# Sensors_and_MCU.net
KiCad netlist of a schematic drawn in Altium Designer
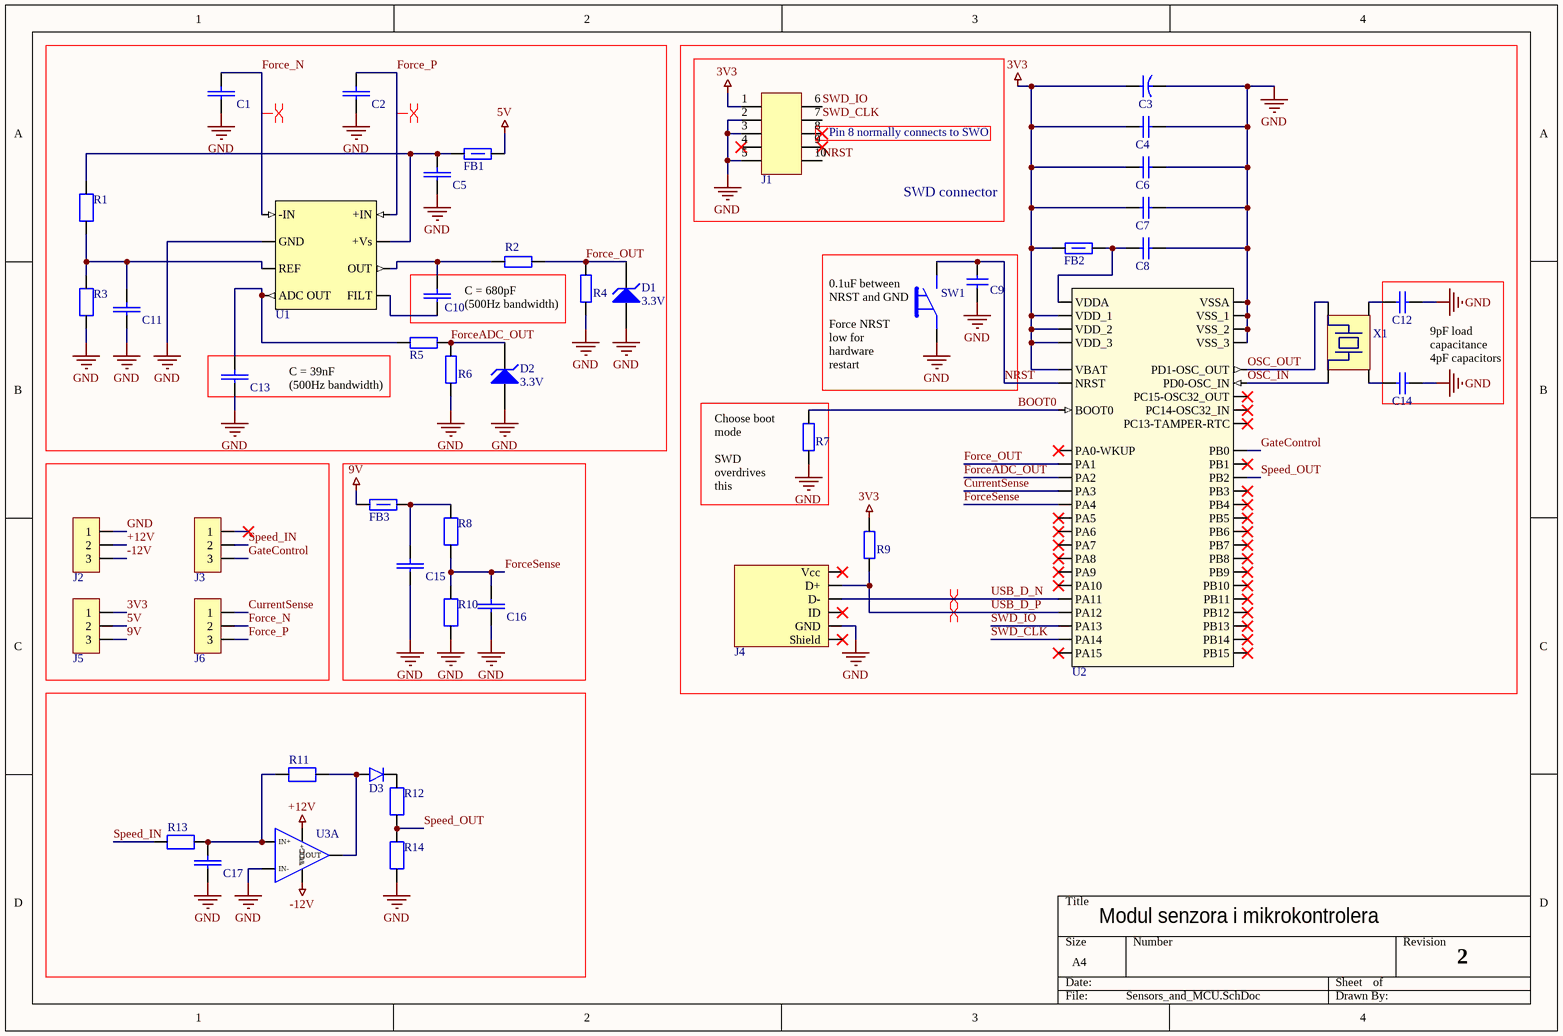
[diagram p0: Sensors_and_MCU.SchDoc]

(export (version "E")
  (design (tool "Eeschema 10.0.6"))
  (components
    (comp (ref "C1")
      (value "Capacitor-NP")
      (footprint "Footprints:C-NP")
      (libsource (lib "Symbols") (part "Capacitor-NP"))
    )
    (comp (ref "C2")
      (value "Capacitor-NP")
      (footprint "Footprints:C-NP")
      (libsource (lib "Symbols") (part "Capacitor-NP"))
    )
    (comp (ref "C3")
      (value "10uF")
      (footprint "CAPAE430X610D540L170X65N")
      (fields
        (field (name "PART NUMBER") "C_10uF_50V")
        (field (name "MANUFACTURER PART NUMBER") "EEE-FK1H100SR")
      )
      (libsource (lib "Database_Libs") (part "Capacitor_P"))
    )
    (comp (ref "C4")
      (value "100nF")
      (footprint "CAPC160X80X87L35N")
      (fields
        (field (name "PART NUMBER") "C_0603_100nF_50V")
        (field (name "MANUFACTURER PART NUMBER") "CC0603MRY5V9BB104")
      )
      (libsource (lib "Database_Libs") (part "Capacitor_NP"))
    )
    (comp (ref "C5")
      (value "Capacitor-NP")
      (footprint "Footprints:C-NP")
      (libsource (lib "Symbols") (part "Capacitor-NP"))
    )
    (comp (ref "C6")
      (value "100nF")
      (footprint "CAPC160X80X87L35N")
      (fields
        (field (name "PART NUMBER") "C_0603_100nF_50V")
        (field (name "MANUFACTURER PART NUMBER") "CC0603MRY5V9BB104")
      )
      (libsource (lib "Database_Libs") (part "Capacitor_NP"))
    )
    (comp (ref "C7")
      (value "100nF")
      (footprint "CAPC160X80X87L35N")
      (fields
        (field (name "PART NUMBER") "C_0603_100nF_50V")
        (field (name "MANUFACTURER PART NUMBER") "CC0603MRY5V9BB104")
      )
      (libsource (lib "Database_Libs") (part "Capacitor_NP"))
    )
    (comp (ref "C8")
      (value "100nF")
      (footprint "CAPC160X80X87L35N")
      (fields
        (field (name "PART NUMBER") "C_0603_100nF_50V")
        (field (name "MANUFACTURER PART NUMBER") "CC0603MRY5V9BB104")
      )
      (libsource (lib "Database_Libs") (part "Capacitor_NP"))
    )
    (comp (ref "C9")
      (value "100nF")
      (footprint "CAPC160X80X87L35N")
      (fields
        (field (name "PART NUMBER") "C_0603_100nF_50V")
        (field (name "MANUFACTURER PART NUMBER") "CC0603MRY5V9BB104")
      )
      (libsource (lib "Database_Libs") (part "Capacitor_NP"))
    )
    (comp (ref "C10")
      (value "Capacitor-NP")
      (footprint "Footprints:C-NP")
      (libsource (lib "Symbols") (part "Capacitor-NP"))
    )
    (comp (ref "C11")
      (value "Capacitor-NP")
      (footprint "Footprints:C-NP")
      (libsource (lib "Symbols") (part "Capacitor-NP"))
    )
    (comp (ref "C12")
      (value "4pF")
      (footprint "CAPC100X50X55L22N")
      (fields
        (field (name "PART NUMBER") "C_0402_4pF_25V")
        (field (name "MANUFACTURER PART NUMBER") "GRM0225C1E4R0CA03L")
      )
      (libsource (lib "Database_Libs") (part "Capacitor_NP"))
    )
    (comp (ref "C13")
      (value "Capacitor-NP")
      (footprint "Footprints:C-NP")
      (libsource (lib "Symbols") (part "Capacitor-NP"))
    )
    (comp (ref "C14")
      (value "4pF")
      (footprint "CAPC100X50X55L22N")
      (fields
        (field (name "PART NUMBER") "C_0402_4pF_25V")
        (field (name "MANUFACTURER PART NUMBER") "GRM0225C1E4R0CA03L")
      )
      (libsource (lib "Database_Libs") (part "Capacitor_NP"))
    )
    (comp (ref "C15")
      (value "Capacitor-NP")
      (footprint "Footprints:C-NP")
      (libsource (lib "Symbols") (part "Capacitor-NP"))
    )
    (comp (ref "C16")
      (value "Capacitor-NP")
      (footprint "Footprints:C-NP")
      (libsource (lib "Symbols") (part "Capacitor-NP"))
    )
    (comp (ref "C17")
      (value "Capacitor-NP")
      (footprint "Footprints:C-NP")
      (libsource (lib "Symbols") (part "Capacitor-NP"))
    )
    (comp (ref "D1")
      (value "Zener Diode")
      (fields (field (name "BV") "3.3V"))
      (libsource (lib "Simulation Generic Components") (part "Zener Diode"))
    )
    (comp (ref "D2")
      (value "Zener Diode")
      (fields (field (name "BV") "3.3V"))
      (libsource (lib "Simulation Generic Components") (part "Zener Diode"))
    )
    (comp (ref "D3")
      (value "Diode")
      (footprint "Footprints:Diode")
      (libsource (lib "Symbols") (part "Diode"))
    )
    (comp (ref "FB1")
      (value "BLM18HE152SH1D")
      (footprint "BEADC160X80X95L30N")
      (libsource (lib "Database_Libs") (part "Ferrite Bead"))
    )
    (comp (ref "FB2")
      (value "BLM18HE152SH1D")
      (footprint "BEADC160X80X95L30N")
      (libsource (lib "Database_Libs") (part "Ferrite Bead"))
    )
    (comp (ref "FB3")
      (value "BLM18HE152SH1D")
      (footprint "BEADC160X80X95L30N")
      (libsource (lib "Database_Libs") (part "Ferrite Bead"))
    )
    (comp (ref "J1")
      (value "Header_10P")
      (footprint "M50-3610542")
      (fields
        (field (name "PART NUMBER") "Header_2x5")
        (field (name "MANUFACTURER PART NUMBER") "M50-3610542")
      )
      (libsource (lib "Database_Libs") (part "Header_2x5"))
    )
    (comp (ref "J2")
      (value "Molex Micro-Latch")
      (footprint "Footprints:ScrewTerminal")
      (fields
        (field (name "PART NUMBER") "Molex Micro-Latch 1x3")
        (field (name "MANUFACTURER PART NUMBER") "53254-0370")
      )
      (libsource (lib "Database_Libs") (part "Header_1x3"))
    )
    (comp (ref "J3")
      (value "Molex Micro-Latch")
      (footprint "Footprints:ScrewTerminal")
      (fields
        (field (name "PART NUMBER") "Molex Micro-Latch 1x3")
        (field (name "MANUFACTURER PART NUMBER") "53254-0370")
      )
      (libsource (lib "Database_Libs") (part "Header_1x3"))
    )
    (comp (ref "J4")
      (value "USB")
      (footprint "USB_mini")
      (fields
        (field (name "PART NUMBER") "USB mini")
        (field (name "MANUFACTURER PART NUMBER") "UJ2-MBH-1-SMT-TR")
      )
      (libsource (lib "Database_Libs") (part "USB_5 pin"))
    )
    (comp (ref "J5")
      (value "Molex Micro-Latch")
      (footprint "Footprints:ScrewTerminal")
      (fields
        (field (name "PART NUMBER") "Molex Micro-Latch 1x3")
        (field (name "MANUFACTURER PART NUMBER") "53254-0370")
      )
      (libsource (lib "Database_Libs") (part "Header_1x3"))
    )
    (comp (ref "J6")
      (value "Molex Micro-Latch")
      (footprint "Footprints:ScrewTerminal")
      (fields
        (field (name "PART NUMBER") "Molex Micro-Latch 1x3")
        (field (name "MANUFACTURER PART NUMBER") "53254-0370")
      )
      (libsource (lib "Database_Libs") (part "Header_1x3"))
    )
    (comp (ref "R1")
      (value "100k")
      (footprint "Footprints:R-2W")
      (libsource (lib "Symbols") (part "Resistor"))
    )
    (comp (ref "R2")
      (value "1.5k")
      (footprint "RESC160X80X50L30N")
      (fields
        (field (name "PART NUMBER") "R_0603_1k5_0W1")
        (field (name "MANUFACTURER PART NUMBER") "RT0603FRE101K5L")
      )
      (libsource (lib "Database_Libs") (part "Resistor"))
    )
    (comp (ref "R3")
      (value "47k")
      (footprint "Footprints:R-2W")
      (libsource (lib "Symbols") (part "Resistor"))
    )
    (comp (ref "R4")
      (value "1.5k")
      (footprint "RESC160X80X50L30N")
      (fields
        (field (name "PART NUMBER") "R_0603_1k5_0W1")
        (field (name "MANUFACTURER PART NUMBER") "RT0603FRE101K5L")
      )
      (libsource (lib "Database_Libs") (part "Resistor"))
    )
    (comp (ref "R5")
      (value "1.5k")
      (footprint "RESC160X80X50L30N")
      (fields
        (field (name "PART NUMBER") "R_0603_1k5_0W1")
        (field (name "MANUFACTURER PART NUMBER") "RT0603FRE101K5L")
      )
      (libsource (lib "Database_Libs") (part "Resistor"))
    )
    (comp (ref "R6")
      (value "1.5k")
      (footprint "RESC160X80X50L30N")
      (fields
        (field (name "PART NUMBER") "R_0603_1k5_0W1")
        (field (name "MANUFACTURER PART NUMBER") "RT0603FRE101K5L")
      )
      (libsource (lib "Database_Libs") (part "Resistor"))
    )
    (comp (ref "R7")
      (value "1.5k")
      (footprint "RESC160X80X50L30N")
      (fields
        (field (name "PART NUMBER") "R_0603_1k5_0W1")
        (field (name "MANUFACTURER PART NUMBER") "RT0603FRE101K5L")
      )
      (libsource (lib "Database_Libs") (part "Resistor"))
    )
    (comp (ref "R8")
      (value "200k")
      (footprint "Footprints:R-2W")
      (libsource (lib "Symbols") (part "Resistor"))
    )
    (comp (ref "R9")
      (value "1.5k")
      (footprint "RESC160X80X50L30N")
      (fields
        (field (name "PART NUMBER") "R_0603_1k5_0W1")
        (field (name "MANUFACTURER PART NUMBER") "RT0603FRE101K5L")
      )
      (libsource (lib "Database_Libs") (part "Resistor"))
    )
    (comp (ref "R10")
      (value "100k")
      (footprint "Footprints:R-2W")
      (libsource (lib "Symbols") (part "Resistor"))
    )
    (comp (ref "R11") (value "220k") (footprint "Footprints:R-2W") (libsource (lib "") (part "Resistor_1")))
    (comp (ref "R12")
      (value "10k")
      (footprint "Footprints:R-2W")
      (libsource (lib "Symbols") (part "Resistor"))
    )
    (comp (ref "R13") (value "1k") (footprint "Footprints:R-2W") (libsource (lib "") (part "Resistor_1")))
    (comp (ref "R14")
      (value "3.3k")
      (footprint "Footprints:R-2W")
      (libsource (lib "Symbols") (part "Resistor"))
    )
    (comp (ref "SW1")
      (value "DTSM-62N-V-T/R")
      (footprint "DTSM62")
      (libsource (lib "Database_Libs") (part "SW_NO_Tactile"))
    )
    (comp (ref "U1")
      (value "AD8293G160ARJZ")
      (footprint "SOT23-8P65_280X145L45X30N")
      (fields (field (name "MANUFACTURER PART NUMBER") "AD8293G160ARJZ-R7"))
      (libsource (lib "Database_Libs") (part "AD8293G160ARJZ"))
    )
    (comp (ref "U2")
      (value "STM32F103CB")
      (footprint "QFP48P50_900X900X160L60X22N")
      (fields (field (name "MANUFACTURER PART NUMBER") "STM32F103CBT6"))
      (libsource (lib "Database_Libs") (part "STM32F103CB"))
    )
    (comp (ref "U3")
      (value "RC4558P")
      (footprint "DIP1092W45P254L959H508Q8")
      (libsource (lib "Database_Libs") (part "RC4558P"))
    )
    (comp (ref "X1")
      (value "16 MHz")
      (footprint "OSCCC320X250X60L90X110N")
      (fields
        (field (name "PART NUMBER") "X_16MHZ_9pF")
        (field (name "MANUFACTURER PART NUMBER") "TSX-3225 16.0000MF09Z-AC3")
      )
      (libsource (lib "Database_Libs") (part "OSC_4pin"))
    )
  )
  (nets
    (net (code "1") (name "+12V") (class "Default")
      (node (ref "J2") (pin "2") (pinfunction "2_2") (pintype "passive"))
      (node (ref "U3") (pin "8") (pinfunction "VCC+_8") (pintype "power_in"))
    )
    (net (code "2") (name "-12V") (class "Default")
      (node (ref "J2") (pin "3") (pinfunction "3_3") (pintype "passive"))
      (node (ref "U3") (pin "4") (pinfunction "VCC-_4") (pintype "power_in"))
    )
    (net (code "3") (name "/BOOT0") (class "Default")
      (node (ref "R7") (pin "2") (pinfunction "2_2") (pintype "passive"))
      (node (ref "U2") (pin "44") (pinfunction "BOOT0_44") (pintype "input"))
    )
    (net (code "4") (name "/CurrentSense") (class "Default")
      (node (ref "J6") (pin "1") (pinfunction "1_1") (pintype "passive"))
      (node (ref "U2") (pin "13") (pinfunction "PA3_13") (pintype "bidirectional"))
    )
    (net (code "5") (name "/ForceADC_OUT") (class "Default")
      (node (ref "D2") (pin "2") (pinfunction "K_2") (pintype "passive"))
      (node (ref "R5") (pin "1") (pinfunction "1_1") (pintype "passive"))
      (node (ref "R6") (pin "1") (pinfunction "1_1") (pintype "passive"))
      (node (ref "U2") (pin "12") (pinfunction "PA2_12") (pintype "bidirectional"))
    )
    (net (code "6") (name "/ForceSense") (class "Default")
      (node (ref "C16") (pin "2") (pinfunction "2_2") (pintype "passive"))
      (node (ref "R10") (pin "2") (pinfunction "2_2") (pintype "passive"))
      (node (ref "R8") (pin "1") (pinfunction "1_1") (pintype "passive"))
      (node (ref "U2") (pin "14") (pinfunction "PA4_14") (pintype "bidirectional"))
    )
    (net (code "7") (name "/Force_N") (class "Default")
      (node (ref "C1") (pin "2") (pinfunction "2_2") (pintype "passive"))
      (node (ref "J6") (pin "2") (pinfunction "2_2") (pintype "passive"))
      (node (ref "U1") (pin "1") (pinfunction "-IN_1") (pintype "input"))
    )
    (net (code "8") (name "/Force_OUT") (class "Default")
      (node (ref "D1") (pin "2") (pinfunction "K_2") (pintype "passive"))
      (node (ref "R2") (pin "1") (pinfunction "1_1") (pintype "passive"))
      (node (ref "R4") (pin "1") (pinfunction "1_1") (pintype "passive"))
      (node (ref "U2") (pin "11") (pinfunction "PA1_11") (pintype "bidirectional"))
    )
    (net (code "9") (name "/Force_P") (class "Default")
      (node (ref "C2") (pin "2") (pinfunction "2_2") (pintype "passive"))
      (node (ref "J6") (pin "3") (pinfunction "3_3") (pintype "passive"))
      (node (ref "U1") (pin "8") (pinfunction "+IN_8") (pintype "input"))
    )
    (net (code "10") (name "/GateControl") (class "Default")
      (node (ref "J3") (pin "3") (pinfunction "3_3") (pintype "passive"))
      (node (ref "U2") (pin "18") (pinfunction "PB0_18") (pintype "bidirectional"))
    )
    (net (code "11") (name "/NRST") (class "Default")
      (node (ref "C9") (pin "1") (pinfunction "1_1") (pintype "passive"))
      (node (ref "J1") (pin "10") (pinfunction "10_10") (pintype "passive"))
      (node (ref "SW1") (pin "2") (pinfunction "2_2") (pintype "passive"))
      (node (ref "U2") (pin "7") (pinfunction "NRST_7") (pintype "bidirectional"))
    )
    (net (code "12") (name "/OSC_IN") (class "Default")
      (node (ref "U2") (pin "5") (pinfunction "PD0-OSC_IN_5") (pintype "input"))
      (node (ref "X1") (pin "3") (pinfunction "3_3") (pintype "passive"))
    )
    (net (code "13") (name "/OSC_OUT") (class "Default")
      (node (ref "U2") (pin "6") (pinfunction "PD1-OSC_OUT_6") (pintype "output"))
      (node (ref "X1") (pin "1") (pinfunction "1_1") (pintype "passive"))
    )
    (net (code "14") (name "/SWD_CLK") (class "Default")
      (node (ref "J1") (pin "7") (pinfunction "7_7") (pintype "passive"))
      (node (ref "U2") (pin "37") (pinfunction "PA14_37") (pintype "bidirectional"))
    )
    (net (code "15") (name "/SWD_IO") (class "Default")
      (node (ref "J1") (pin "6") (pinfunction "6_6") (pintype "passive"))
      (node (ref "U2") (pin "34") (pinfunction "PA13_34") (pintype "bidirectional"))
    )
    (net (code "16") (name "/Speed_IN") (class "Default")
      (node (ref "J3") (pin "2") (pinfunction "2_2") (pintype "passive"))
      (node (ref "R13") (pin "2") (pinfunction "2_2") (pintype "passive"))
    )
    (net (code "17") (name "/Speed_OUT") (class "Default")
      (node (ref "R12") (pin "1") (pinfunction "1_1") (pintype "passive"))
      (node (ref "R14") (pin "2") (pinfunction "2_2") (pintype "passive"))
      (node (ref "U2") (pin "20") (pinfunction "PB2_20") (pintype "bidirectional"))
    )
    (net (code "18") (name "/USB_D_N") (class "Default")
      (node (ref "J4") (pin "2") (pinfunction "D-_2") (pintype "passive"))
      (node (ref "U2") (pin "32") (pinfunction "PA11_32") (pintype "bidirectional"))
    )
    (net (code "19") (name "/USB_D_P") (class "Default")
      (node (ref "J4") (pin "3") (pinfunction "D+_3") (pintype "passive"))
      (node (ref "R9") (pin "1") (pinfunction "1_1") (pintype "passive"))
      (node (ref "U2") (pin "33") (pinfunction "PA12_33") (pintype "bidirectional"))
    )
    (net (code "20") (name "3V3") (class "Default")
      (node (ref "C3") (pin "1") (pinfunction "1_1") (pintype "passive"))
      (node (ref "C4") (pin "2") (pinfunction "2_2") (pintype "passive"))
      (node (ref "C6") (pin "2") (pinfunction "2_2") (pintype "passive"))
      (node (ref "C7") (pin "2") (pinfunction "2_2") (pintype "passive"))
      (node (ref "FB2") (pin "1") (pinfunction "1_1") (pintype "passive"))
      (node (ref "J1") (pin "1") (pinfunction "1_1") (pintype "passive"))
      (node (ref "J5") (pin "1") (pinfunction "1_1") (pintype "passive"))
      (node (ref "R9") (pin "2") (pinfunction "2_2") (pintype "passive"))
      (node (ref "U2") (pin "1") (pinfunction "VBAT_1") (pintype "power_in"))
      (node (ref "U2") (pin "24") (pinfunction "VDD_1_24") (pintype "power_in"))
      (node (ref "U2") (pin "36") (pinfunction "VDD_2_36") (pintype "power_in"))
      (node (ref "U2") (pin "48") (pinfunction "VDD_3_48") (pintype "power_in"))
    )
    (net (code "21") (name "5V") (class "Default")
      (node (ref "FB1") (pin "2") (pinfunction "2_2") (pintype "passive"))
      (node (ref "J5") (pin "2") (pinfunction "2_2") (pintype "passive"))
    )
    (net (code "22") (name "9V") (class "Default")
      (node (ref "FB3") (pin "1") (pinfunction "1_1") (pintype "passive"))
      (node (ref "J5") (pin "3") (pinfunction "3_3") (pintype "passive"))
    )
    (net (code "23") (name "GND") (class "Default")
      (node (ref "C1") (pin "1") (pinfunction "1_1") (pintype "passive"))
      (node (ref "C11") (pin "1") (pinfunction "1_1") (pintype "passive"))
      (node (ref "C12") (pin "1") (pinfunction "1_1") (pintype "passive"))
      (node (ref "C13") (pin "1") (pinfunction "1_1") (pintype "passive"))
      (node (ref "C14") (pin "1") (pinfunction "1_1") (pintype "passive"))
      (node (ref "C15") (pin "1") (pinfunction "1_1") (pintype "passive"))
      (node (ref "C16") (pin "1") (pinfunction "1_1") (pintype "passive"))
      (node (ref "C17") (pin "1") (pinfunction "1_1") (pintype "passive"))
      (node (ref "C2") (pin "1") (pinfunction "1_1") (pintype "passive"))
      (node (ref "C3") (pin "2") (pinfunction "2_2") (pintype "passive"))
      (node (ref "C4") (pin "1") (pinfunction "1_1") (pintype "passive"))
      (node (ref "C5") (pin "1") (pinfunction "1_1") (pintype "passive"))
      (node (ref "C6") (pin "1") (pinfunction "1_1") (pintype "passive"))
      (node (ref "C7") (pin "1") (pinfunction "1_1") (pintype "passive"))
      (node (ref "C8") (pin "1") (pinfunction "1_1") (pintype "passive"))
      (node (ref "C9") (pin "2") (pinfunction "2_2") (pintype "passive"))
      (node (ref "D1") (pin "1") (pinfunction "A_1") (pintype "passive"))
      (node (ref "D2") (pin "1") (pinfunction "A_1") (pintype "passive"))
      (node (ref "J1") (pin "2") (pinfunction "2_2") (pintype "passive"))
      (node (ref "J1") (pin "3") (pinfunction "3_3") (pintype "passive"))
      (node (ref "J1") (pin "5") (pinfunction "5_5") (pintype "passive"))
      (node (ref "J2") (pin "1") (pinfunction "1_1") (pintype "passive"))
      (node (ref "J4") (pin "5") (pinfunction "GND_5") (pintype "passive"))
      (node (ref "R10") (pin "1") (pinfunction "1_1") (pintype "passive"))
      (node (ref "R14") (pin "1") (pinfunction "1_1") (pintype "passive"))
      (node (ref "R3") (pin "1") (pinfunction "1_1") (pintype "passive"))
      (node (ref "R4") (pin "2") (pinfunction "2_2") (pintype "passive"))
      (node (ref "R6") (pin "2") (pinfunction "2_2") (pintype "passive"))
      (node (ref "R7") (pin "1") (pinfunction "1_1") (pintype "passive"))
      (node (ref "SW1") (pin "1") (pinfunction "1_1") (pintype "passive"))
      (node (ref "U1") (pin "2") (pinfunction "GND_2") (pintype "power_in"))
      (node (ref "U2") (pin "23") (pinfunction "VSS_1_23") (pintype "power_in"))
      (node (ref "U2") (pin "35") (pinfunction "VSS_2_35") (pintype "power_in"))
      (node (ref "U2") (pin "47") (pinfunction "VSS_3_47") (pintype "power_in"))
      (node (ref "U2") (pin "8") (pinfunction "VSSA_8") (pintype "power_in"))
      (node (ref "U3") (pin "2") (pinfunction "IN-_2") (pintype "passive"))
    )
    (net (code "24") (name "Net-(C12-Pad2)") (class "Default")
      (node (ref "C12") (pin "2") (pinfunction "2_2") (pintype "passive"))
      (node (ref "X1") (pin "2") (pinfunction "2_2") (pintype "passive"))
    )
    (net (code "25") (name "Net-(C14-Pad2)") (class "Default")
      (node (ref "C14") (pin "2") (pinfunction "2_2") (pintype "passive"))
      (node (ref "X1") (pin "4") (pinfunction "4_4") (pintype "passive"))
    )
    (net (code "26") (name "Net-(C15-Pad2)") (class "Default")
      (node (ref "C15") (pin "2") (pinfunction "2_2") (pintype "passive"))
      (node (ref "FB3") (pin "2") (pinfunction "2_2") (pintype "passive"))
      (node (ref "R8") (pin "2") (pinfunction "2_2") (pintype "passive"))
    )
    (net (code "27") (name "Net-(D3-PadC)") (class "Default")
      (node (ref "D3") (pin "C") (pinfunction "C_C") (pintype "passive"))
      (node (ref "R12") (pin "2") (pinfunction "2_2") (pintype "passive"))
    )
    (net (code "28") (name "Net-(U1-+Vs)") (class "Default")
      (node (ref "C5") (pin "2") (pinfunction "2_2") (pintype "passive"))
      (node (ref "FB1") (pin "1") (pinfunction "1_1") (pintype "passive"))
      (node (ref "R1") (pin "2") (pinfunction "2_2") (pintype "passive"))
      (node (ref "U1") (pin "7") (pinfunction "+Vs_7") (pintype "passive"))
    )
    (net (code "29") (name "Net-(U1-ADC_OUT)") (class "Default")
      (node (ref "C13") (pin "2") (pinfunction "2_2") (pintype "passive"))
      (node (ref "R5") (pin "2") (pinfunction "2_2") (pintype "passive"))
      (node (ref "U1") (pin "4") (pinfunction "ADC_OUT_4") (pintype "output"))
    )
    (net (code "30") (name "Net-(U1-FILT)") (class "Default")
      (node (ref "C10") (pin "1") (pinfunction "1_1") (pintype "passive"))
      (node (ref "U1") (pin "5") (pinfunction "FILT_5") (pintype "passive"))
    )
    (net (code "31") (name "Net-(U1-OUT)") (class "Default")
      (node (ref "C10") (pin "2") (pinfunction "2_2") (pintype "passive"))
      (node (ref "R2") (pin "2") (pinfunction "2_2") (pintype "passive"))
      (node (ref "U1") (pin "6") (pinfunction "OUT_6") (pintype "output"))
    )
    (net (code "32") (name "Net-(U1-REF)") (class "Default")
      (node (ref "C11") (pin "2") (pinfunction "2_2") (pintype "passive"))
      (node (ref "R1") (pin "1") (pinfunction "1_1") (pintype "passive"))
      (node (ref "R3") (pin "2") (pinfunction "2_2") (pintype "passive"))
      (node (ref "U1") (pin "3") (pinfunction "REF_3") (pintype "passive"))
    )
    (net (code "33") (name "Net-(U2-VDDA)") (class "Default")
      (node (ref "C8") (pin "2") (pinfunction "2_2") (pintype "passive"))
      (node (ref "FB2") (pin "2") (pinfunction "2_2") (pintype "passive"))
      (node (ref "U2") (pin "9") (pinfunction "VDDA_9") (pintype "power_in"))
    )
    (net (code "34") (name "Net-(U3A-IN+)") (class "Default")
      (node (ref "C17") (pin "2") (pinfunction "2_2") (pintype "passive"))
      (node (ref "R11") (pin "2") (pinfunction "2_2") (pintype "passive"))
      (node (ref "R13") (pin "1") (pinfunction "1_1") (pintype "passive"))
      (node (ref "U3") (pin "3") (pinfunction "IN+_3") (pintype "passive"))
    )
    (net (code "35") (name "Net-(U3A-OUT)") (class "Default")
      (node (ref "D3") (pin "A") (pinfunction "A_A") (pintype "passive"))
      (node (ref "R11") (pin "1") (pinfunction "1_1") (pintype "passive"))
      (node (ref "U3") (pin "1") (pinfunction "OUT_1") (pintype "passive"))
    )
    (net (code "36") (name "unconnected-(J1-Pad4)") (class "Default")
      (node (ref "J1") (pin "4") (pinfunction "4_4") (pintype "passive+no_connect"))
    )
    (net (code "37") (name "unconnected-(J1-Pad8)") (class "Default")
      (node (ref "J1") (pin "8") (pinfunction "8_8") (pintype "passive+no_connect"))
    )
    (net (code "38") (name "unconnected-(J1-Pad9)") (class "Default")
      (node (ref "J1") (pin "9") (pinfunction "9_9") (pintype "passive+no_connect"))
    )
    (net (code "39") (name "unconnected-(J3-Pad1)") (class "Default")
      (node (ref "J3") (pin "1") (pinfunction "1_1") (pintype "passive+no_connect"))
    )
    (net (code "40") (name "unconnected-(J4-ID-Pad4)") (class "Default")
      (node (ref "J4") (pin "4") (pinfunction "ID_4") (pintype "passive+no_connect"))
    )
    (net (code "41") (name "unconnected-(J4-Shield-Pad6)") (class "Default")
      (node (ref "J4") (pin "6") (pinfunction "Shield_6") (pintype "passive+no_connect"))
    )
    (net (code "42") (name "unconnected-(J4-Vcc-Pad1)") (class "Default")
      (node (ref "J4") (pin "1") (pinfunction "Vcc_1") (pintype "passive+no_connect"))
    )
    (net (code "43") (name "unconnected-(U2-PA0-WKUP-Pad10)") (class "Default")
      (node (ref "U2") (pin "10") (pinfunction "PA0-WKUP_10") (pintype "bidirectional+no_connect"))
    )
    (net (code "44") (name "unconnected-(U2-PA5-Pad15)") (class "Default")
      (node (ref "U2") (pin "15") (pinfunction "PA5_15") (pintype "bidirectional+no_connect"))
    )
    (net (code "45") (name "unconnected-(U2-PA6-Pad16)") (class "Default")
      (node (ref "U2") (pin "16") (pinfunction "PA6_16") (pintype "bidirectional+no_connect"))
    )
    (net (code "46") (name "unconnected-(U2-PA7-Pad17)") (class "Default")
      (node (ref "U2") (pin "17") (pinfunction "PA7_17") (pintype "bidirectional+no_connect"))
    )
    (net (code "47") (name "unconnected-(U2-PA8-Pad29)") (class "Default")
      (node (ref "U2") (pin "29") (pinfunction "PA8_29") (pintype "bidirectional+no_connect"))
    )
    (net (code "48") (name "unconnected-(U2-PA9-Pad30)") (class "Default")
      (node (ref "U2") (pin "30") (pinfunction "PA9_30") (pintype "bidirectional+no_connect"))
    )
    (net (code "49") (name "unconnected-(U2-PA10-Pad31)") (class "Default")
      (node (ref "U2") (pin "31") (pinfunction "PA10_31") (pintype "bidirectional+no_connect"))
    )
    (net (code "50") (name "unconnected-(U2-PA15-Pad38)") (class "Default")
      (node (ref "U2") (pin "38") (pinfunction "PA15_38") (pintype "bidirectional+no_connect"))
    )
    (net (code "51") (name "unconnected-(U2-PB1-Pad19)") (class "Default")
      (node (ref "U2") (pin "19") (pinfunction "PB1_19") (pintype "bidirectional+no_connect"))
    )
    (net (code "52") (name "unconnected-(U2-PB3-Pad39)") (class "Default")
      (node (ref "U2") (pin "39") (pinfunction "PB3_39") (pintype "bidirectional+no_connect"))
    )
    (net (code "53") (name "unconnected-(U2-PB4-Pad40)") (class "Default")
      (node (ref "U2") (pin "40") (pinfunction "PB4_40") (pintype "bidirectional+no_connect"))
    )
    (net (code "54") (name "unconnected-(U2-PB5-Pad41)") (class "Default")
      (node (ref "U2") (pin "41") (pinfunction "PB5_41") (pintype "bidirectional+no_connect"))
    )
    (net (code "55") (name "unconnected-(U2-PB6-Pad42)") (class "Default")
      (node (ref "U2") (pin "42") (pinfunction "PB6_42") (pintype "bidirectional+no_connect"))
    )
    (net (code "56") (name "unconnected-(U2-PB7-Pad43)") (class "Default")
      (node (ref "U2") (pin "43") (pinfunction "PB7_43") (pintype "bidirectional+no_connect"))
    )
    (net (code "57") (name "unconnected-(U2-PB8-Pad45)") (class "Default")
      (node (ref "U2") (pin "45") (pinfunction "PB8_45") (pintype "bidirectional+no_connect"))
    )
    (net (code "58") (name "unconnected-(U2-PB9-Pad46)") (class "Default")
      (node (ref "U2") (pin "46") (pinfunction "PB9_46") (pintype "bidirectional+no_connect"))
    )
    (net (code "59") (name "unconnected-(U2-PB10-Pad21)") (class "Default")
      (node (ref "U2") (pin "21") (pinfunction "PB10_21") (pintype "bidirectional+no_connect"))
    )
    (net (code "60") (name "unconnected-(U2-PB11-Pad22)") (class "Default")
      (node (ref "U2") (pin "22") (pinfunction "PB11_22") (pintype "bidirectional+no_connect"))
    )
    (net (code "61") (name "unconnected-(U2-PB12-Pad25)") (class "Default")
      (node (ref "U2") (pin "25") (pinfunction "PB12_25") (pintype "bidirectional+no_connect"))
    )
    (net (code "62") (name "unconnected-(U2-PB13-Pad26)") (class "Default")
      (node (ref "U2") (pin "26") (pinfunction "PB13_26") (pintype "bidirectional+no_connect"))
    )
    (net (code "63") (name "unconnected-(U2-PB14-Pad27)") (class "Default")
      (node (ref "U2") (pin "27") (pinfunction "PB14_27") (pintype "bidirectional+no_connect"))
    )
    (net (code "64") (name "unconnected-(U2-PB15-Pad28)") (class "Default")
      (node (ref "U2") (pin "28") (pinfunction "PB15_28") (pintype "bidirectional+no_connect"))
    )
    (net (code "65") (name "unconnected-(U2-PC13-TAMPER-RTC-Pad2)") (class "Default")
      (node (ref "U2") (pin "2") (pinfunction "PC13-TAMPER-RTC_2") (pintype "bidirectional+no_connect"))
    )
    (net (code "66") (name "unconnected-(U2-PC14-OSC32_IN-Pad3)") (class "Default")
      (node (ref "U2") (pin "3") (pinfunction "PC14-OSC32_IN_3") (pintype "bidirectional+no_connect"))
    )
    (net (code "67") (name "unconnected-(U2-PC15-OSC32_OUT-Pad4)") (class "Default")
      (node (ref "U2") (pin "4") (pinfunction "PC15-OSC32_OUT_4") (pintype "bidirectional+no_connect"))
    )
  )
)
